# CC40_RAM_Cart.net
KiCad netlist of a schematic drawn in EAGLE
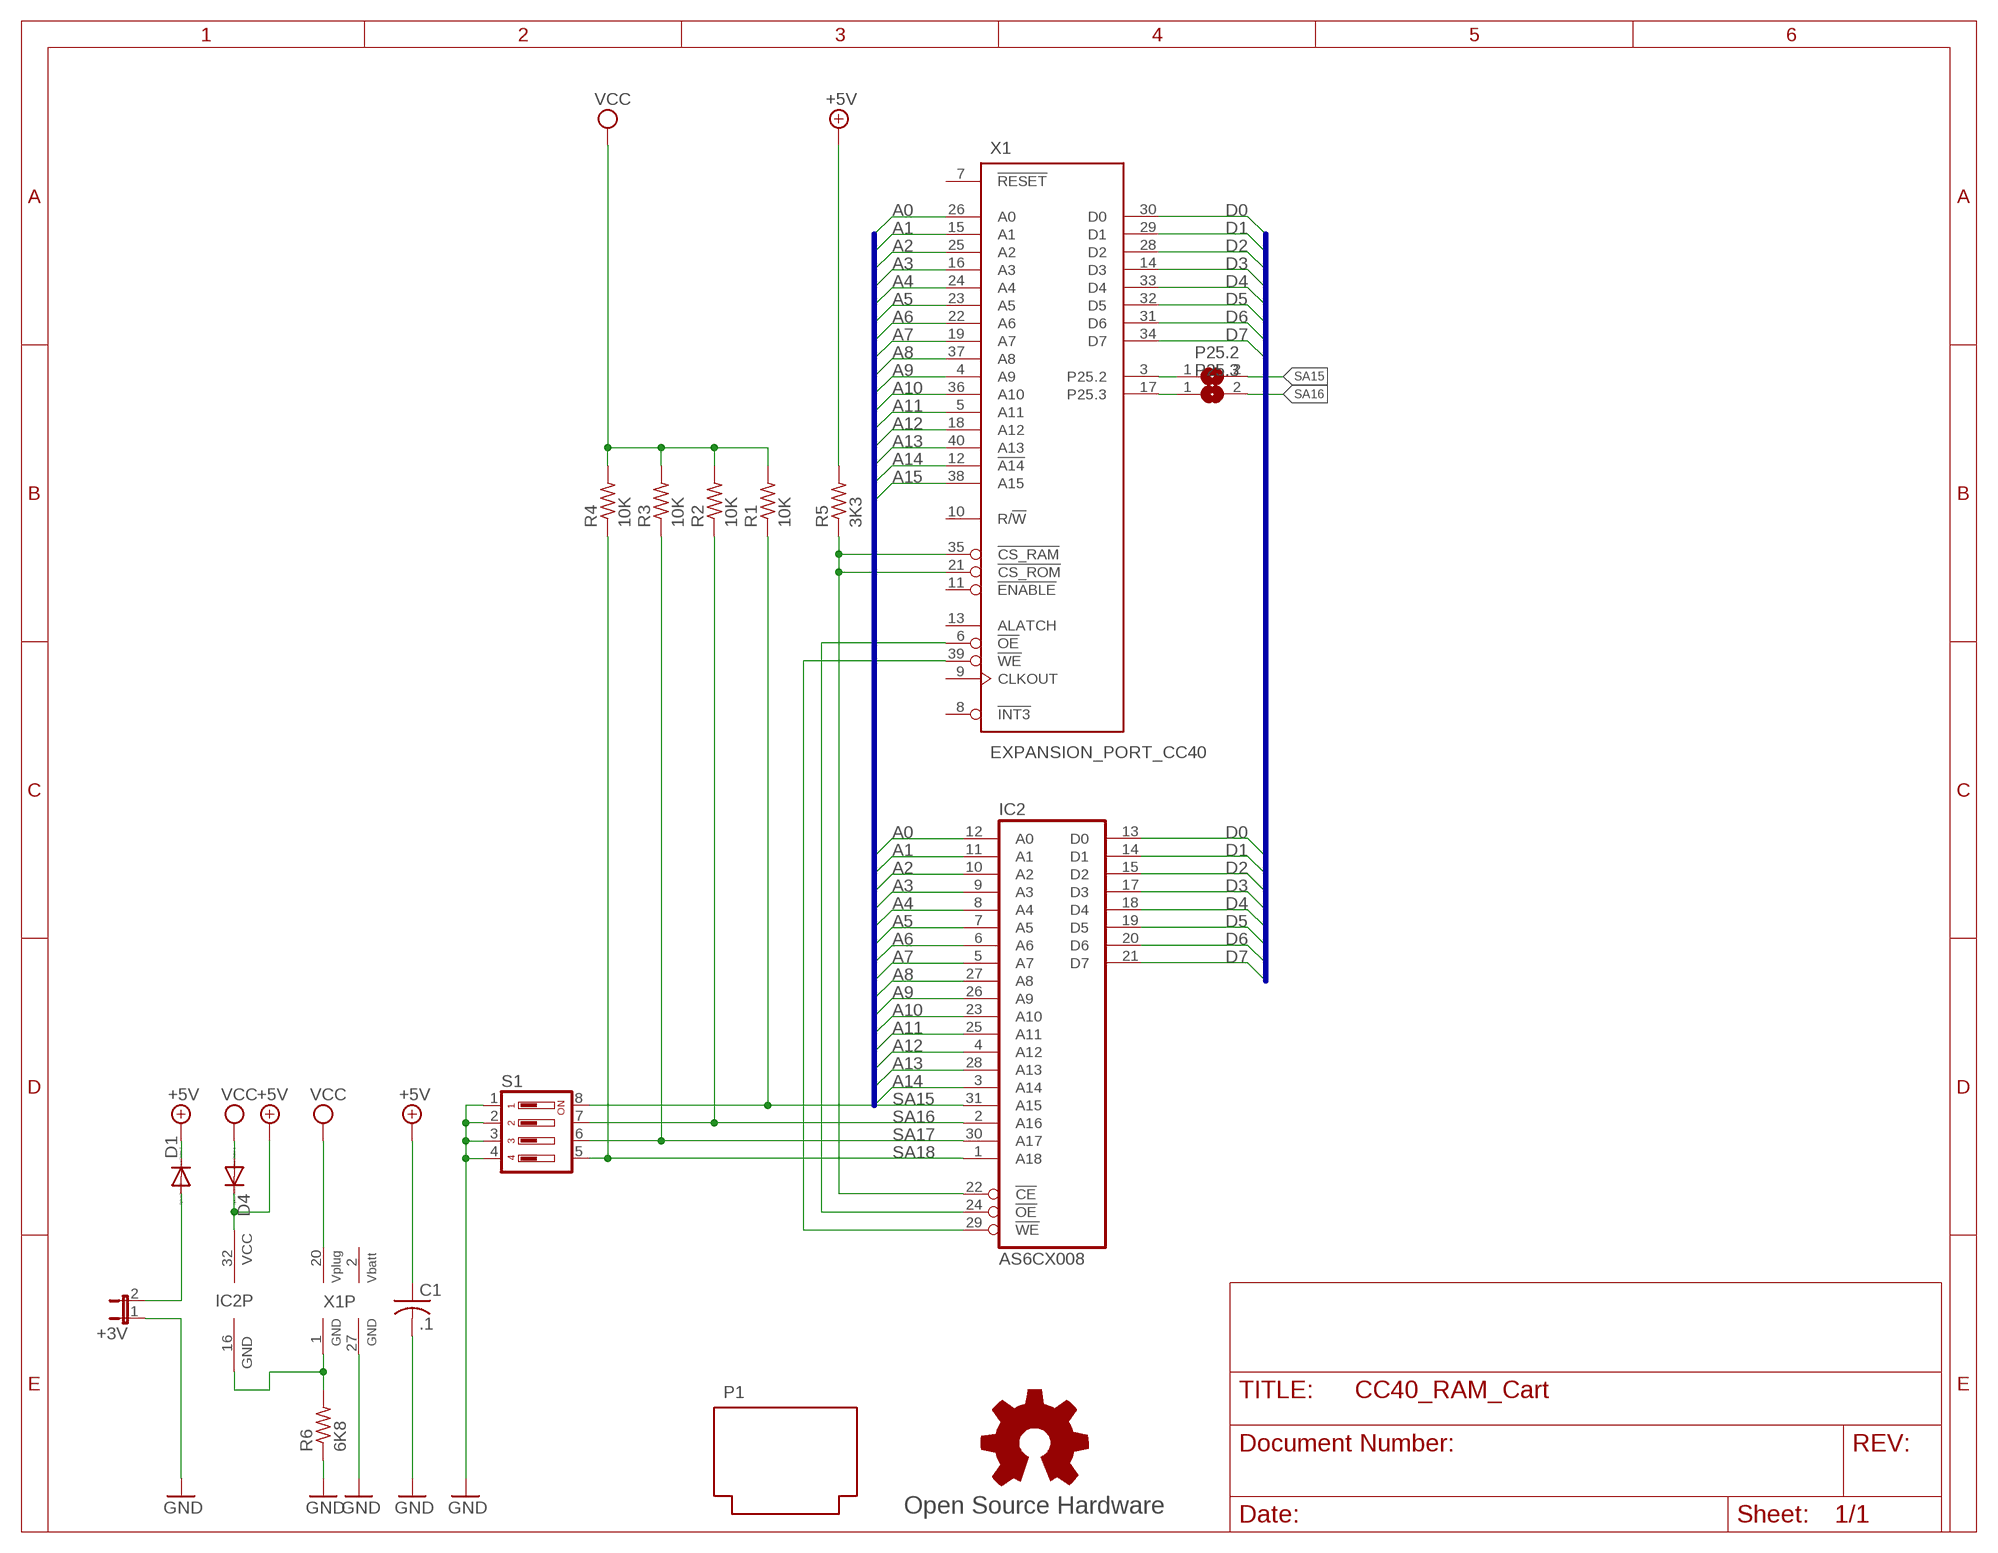
[diagram p0: schematic, sheet 1]

(export (version "E")
  (design (tool "Eeschema 10.0.6"))
  (components
    (comp (ref "+3V")
      (value "JP1E")
      (footprint "eagle-import:JP1")
      (libsource (lib "eagle-import") (part "JP1E"))
    )
    (comp (ref "C1")
      (value ".1")
      (footprint "eagle-import:C025-025X050")
      (libsource (lib "eagle-import") (part "C-US025-025X050"))
    )
    (comp (ref "D1")
      (value "DIODE-D-5")
      (footprint "eagle-import:D-5")
      (libsource (lib "eagle-import") (part "DIODE-D-5"))
    )
    (comp (ref "D4")
      (value "DIODE-D-5")
      (footprint "eagle-import:D-5")
      (libsource (lib "eagle-import") (part "DIODE-D-5"))
    )
    (comp (ref "GOLD_ORB_SM1")
      (value "Open Source Hardware")
      (footprint "eagle-import:OSHW_8MM")
      (libsource (lib "eagle-import") (part "OSHWLOGOLOGO8MM"))
    )
    (comp (ref "IC2")
      (value "AS6CX008")
      (footprint "eagle-import:DIL32-RP")
      (libsource (lib "eagle-import") (part "AS6C4008PCNR"))
    )
    (comp (ref "P1")
      (value "CC40_CARTN")
      (footprint "eagle-import:CC40_CART_NOHOLE")
      (libsource (lib "eagle-import") (part "CC40_CARTN"))
    )
    (comp (ref "P25.2")
      (value "SJ")
      (footprint "eagle-import:SJ")
      (libsource (lib "eagle-import") (part "SJ"))
    )
    (comp (ref "P25.3")
      (value "SJ")
      (footprint "eagle-import:SJ")
      (libsource (lib "eagle-import") (part "SJ"))
    )
    (comp (ref "R1")
      (value "10K")
      (footprint "eagle-import:0204_7")
      (libsource (lib "eagle-import") (part "R-US_0204/7"))
    )
    (comp (ref "R2")
      (value "10K")
      (footprint "eagle-import:0204_7")
      (libsource (lib "eagle-import") (part "R-US_0204/7"))
    )
    (comp (ref "R3")
      (value "10K")
      (footprint "eagle-import:0204_7")
      (libsource (lib "eagle-import") (part "R-US_0204/7"))
    )
    (comp (ref "R4")
      (value "10K")
      (footprint "eagle-import:0204_7")
      (libsource (lib "eagle-import") (part "R-US_0204/7"))
    )
    (comp (ref "R5")
      (value "3K3")
      (footprint "eagle-import:0204_7")
      (libsource (lib "eagle-import") (part "R-US_0204/7"))
    )
    (comp (ref "R6")
      (value "6K8")
      (footprint "eagle-import:0204_7")
      (libsource (lib "eagle-import") (part "R-US_0204/7"))
    )
    (comp (ref "S1")
      (value "DP04")
      (footprint "eagle-import:DP-04")
      (libsource (lib "eagle-import") (part "DP04"))
    )
    (comp (ref "X1")
      (value "EXPANSION_PORT_CC40")
      (footprint "eagle-import:MA20-2(.050)")
      (libsource (lib "eagle-import") (part "EXPANSION_PORT_CC40"))
    )
  )
  (nets
    (net (code "1") (name "+5V") (class "Default")
      (node (ref "C1") (pin "1") (pinfunction "1_1") (pintype "passive"))
      (node (ref "D1") (pin "C") (pinfunction "C_C") (pintype "passive"))
      (node (ref "D4") (pin "C") (pinfunction "C_C") (pintype "passive"))
      (node (ref "IC2") (pin "32") (pinfunction "VCC_32") (pintype "power_in"))
      (node (ref "R5") (pin "2") (pinfunction "2_2") (pintype "passive"))
    )
    (net (code "2") (name "/A0") (class "Default")
      (node (ref "IC2") (pin "12") (pinfunction "A0_12") (pintype "input"))
      (node (ref "X1") (pin "26") (pinfunction "A0_26") (pintype "output"))
    )
    (net (code "3") (name "/A1") (class "Default")
      (node (ref "IC2") (pin "11") (pinfunction "A1_11") (pintype "input"))
      (node (ref "X1") (pin "15") (pinfunction "A1_15") (pintype "output"))
    )
    (net (code "4") (name "/A2") (class "Default")
      (node (ref "IC2") (pin "10") (pinfunction "A2_10") (pintype "input"))
      (node (ref "X1") (pin "25") (pinfunction "A2_25") (pintype "output"))
    )
    (net (code "5") (name "/A3") (class "Default")
      (node (ref "IC2") (pin "9") (pinfunction "A3_9") (pintype "input"))
      (node (ref "X1") (pin "16") (pinfunction "A3_16") (pintype "output"))
    )
    (net (code "6") (name "/A4") (class "Default")
      (node (ref "IC2") (pin "8") (pinfunction "A4_8") (pintype "input"))
      (node (ref "X1") (pin "24") (pinfunction "A4_24") (pintype "output"))
    )
    (net (code "7") (name "/A5") (class "Default")
      (node (ref "IC2") (pin "7") (pinfunction "A5_7") (pintype "input"))
      (node (ref "X1") (pin "23") (pinfunction "A5_23") (pintype "output"))
    )
    (net (code "8") (name "/A6") (class "Default")
      (node (ref "IC2") (pin "6") (pinfunction "A6_6") (pintype "input"))
      (node (ref "X1") (pin "22") (pinfunction "A6_22") (pintype "output"))
    )
    (net (code "9") (name "/A7") (class "Default")
      (node (ref "IC2") (pin "5") (pinfunction "A7_5") (pintype "input"))
      (node (ref "X1") (pin "19") (pinfunction "A7_19") (pintype "output"))
    )
    (net (code "10") (name "/A8") (class "Default")
      (node (ref "IC2") (pin "27") (pinfunction "A8_27") (pintype "input"))
      (node (ref "X1") (pin "37") (pinfunction "A8_37") (pintype "output"))
    )
    (net (code "11") (name "/A9") (class "Default")
      (node (ref "IC2") (pin "26") (pinfunction "A9_26") (pintype "input"))
      (node (ref "X1") (pin "4") (pinfunction "A9_4") (pintype "output"))
    )
    (net (code "12") (name "/A10") (class "Default")
      (node (ref "IC2") (pin "23") (pinfunction "A10_23") (pintype "input"))
      (node (ref "X1") (pin "36") (pinfunction "A10_36") (pintype "passive"))
    )
    (net (code "13") (name "/A11") (class "Default")
      (node (ref "IC2") (pin "25") (pinfunction "A11_25") (pintype "input"))
      (node (ref "X1") (pin "5") (pinfunction "A11_5") (pintype "output"))
    )
    (net (code "14") (name "/A12") (class "Default")
      (node (ref "IC2") (pin "4") (pinfunction "A12_4") (pintype "input"))
      (node (ref "X1") (pin "18") (pinfunction "A12_18") (pintype "output"))
    )
    (net (code "15") (name "/A13") (class "Default")
      (node (ref "IC2") (pin "28") (pinfunction "A13_28") (pintype "input"))
      (node (ref "X1") (pin "40") (pinfunction "A13_40") (pintype "output"))
    )
    (net (code "16") (name "/A14") (class "Default")
      (node (ref "IC2") (pin "3") (pinfunction "A14_3") (pintype "input"))
      (node (ref "X1") (pin "12") (pinfunction "~{A14}_12") (pintype "output"))
    )
    (net (code "17") (name "/A15") (class "Default")
      (node (ref "X1") (pin "38") (pinfunction "A15_38") (pintype "output"))
    )
    (net (code "18") (name "/D0") (class "Default")
      (node (ref "IC2") (pin "13") (pinfunction "D0_13") (pintype "bidirectional"))
      (node (ref "X1") (pin "30") (pinfunction "D0_30") (pintype "bidirectional"))
    )
    (net (code "19") (name "/D1") (class "Default")
      (node (ref "IC2") (pin "14") (pinfunction "D1_14") (pintype "bidirectional"))
      (node (ref "X1") (pin "29") (pinfunction "D1_29") (pintype "bidirectional"))
    )
    (net (code "20") (name "/D2") (class "Default")
      (node (ref "IC2") (pin "15") (pinfunction "D2_15") (pintype "bidirectional"))
      (node (ref "X1") (pin "28") (pinfunction "D2_28") (pintype "bidirectional"))
    )
    (net (code "21") (name "/D3") (class "Default")
      (node (ref "IC2") (pin "17") (pinfunction "D3_17") (pintype "bidirectional"))
      (node (ref "X1") (pin "14") (pinfunction "D3_14") (pintype "bidirectional"))
    )
    (net (code "22") (name "/D4") (class "Default")
      (node (ref "IC2") (pin "18") (pinfunction "D4_18") (pintype "bidirectional"))
      (node (ref "X1") (pin "33") (pinfunction "D4_33") (pintype "bidirectional"))
    )
    (net (code "23") (name "/D5") (class "Default")
      (node (ref "IC2") (pin "19") (pinfunction "D5_19") (pintype "bidirectional"))
      (node (ref "X1") (pin "32") (pinfunction "D5_32") (pintype "bidirectional"))
    )
    (net (code "24") (name "/D6") (class "Default")
      (node (ref "IC2") (pin "20") (pinfunction "D6_20") (pintype "bidirectional"))
      (node (ref "X1") (pin "31") (pinfunction "D6_31") (pintype "bidirectional"))
    )
    (net (code "25") (name "/D7") (class "Default")
      (node (ref "IC2") (pin "21") (pinfunction "D7_21") (pintype "bidirectional"))
      (node (ref "X1") (pin "34") (pinfunction "D7_34") (pintype "bidirectional"))
    )
    (net (code "26") (name "/SA17") (class "Default")
      (node (ref "IC2") (pin "30") (pinfunction "A17_30") (pintype "input"))
      (node (ref "R3") (pin "1") (pinfunction "1_1") (pintype "passive"))
      (node (ref "S1") (pin "6") (pinfunction "6_6") (pintype "passive"))
    )
    (net (code "27") (name "/SA18") (class "Default")
      (node (ref "IC2") (pin "1") (pinfunction "A18_1") (pintype "input"))
      (node (ref "R4") (pin "1") (pinfunction "1_1") (pintype "passive"))
      (node (ref "S1") (pin "5") (pinfunction "5_5") (pintype "passive"))
    )
    (net (code "28") (name "/VBATT") (class "Default")
      (node (ref "X1") (pin "2") (pinfunction "VBATT_2") (pintype "power_in"))
    )
    (net (code "29") (name "GND") (class "Default")
      (node (ref "+3V") (pin "1") (pinfunction "1_1") (pintype "passive"))
      (node (ref "C1") (pin "2") (pinfunction "2_2") (pintype "passive"))
      (node (ref "R6") (pin "1") (pinfunction "1_1") (pintype "passive"))
      (node (ref "S1") (pin "1") (pinfunction "1_1") (pintype "passive"))
      (node (ref "S1") (pin "2") (pinfunction "2_2") (pintype "passive"))
      (node (ref "S1") (pin "3") (pinfunction "3_3") (pintype "passive"))
      (node (ref "S1") (pin "4") (pinfunction "4_4") (pintype "passive"))
      (node (ref "X1") (pin "27") (pinfunction "GND_27") (pintype "power_in"))
    )
    (net (code "30") (name "Net-(+3V-Pad2)") (class "Default")
      (node (ref "+3V") (pin "2") (pinfunction "2_2") (pintype "passive"))
      (node (ref "D1") (pin "A") (pinfunction "A_A") (pintype "passive"))
    )
    (net (code "31") (name "Net-(IC2A-~{CE})") (class "Default")
      (node (ref "IC2") (pin "22") (pinfunction "~{CE}_22") (pintype "input"))
      (node (ref "R5") (pin "1") (pinfunction "1_1") (pintype "passive"))
      (node (ref "X1") (pin "21") (pinfunction "~{CS_ROM}_21") (pintype "output"))
      (node (ref "X1") (pin "35") (pinfunction "~{CS_RAM}_35") (pintype "output"))
    )
    (net (code "32") (name "Net-(IC2A-~{OE})") (class "Default")
      (node (ref "IC2") (pin "24") (pinfunction "~{OE}_24") (pintype "input"))
      (node (ref "X1") (pin "6") (pinfunction "~{OE}_6") (pintype "output"))
    )
    (net (code "33") (name "Net-(IC2A-~{WE})") (class "Default")
      (node (ref "IC2") (pin "29") (pinfunction "~{WE}_29") (pintype "input"))
      (node (ref "X1") (pin "39") (pinfunction "~{WE}_39") (pintype "output"))
    )
    (net (code "34") (name "Net-(IC2B-GND)") (class "Default")
      (node (ref "IC2") (pin "16") (pinfunction "GND_16") (pintype "power_in"))
      (node (ref "R6") (pin "2") (pinfunction "2_2") (pintype "passive"))
      (node (ref "X1") (pin "1") (pinfunction "GND_1") (pintype "power_in"))
    )
    (net (code "35") (name "Net-(X1B-P25.2)") (class "Default")
      (node (ref "P25.2") (pin "1") (pinfunction "1_1") (pintype "passive"))
      (node (ref "X1") (pin "3") (pinfunction "P25.2_3") (pintype "bidirectional"))
    )
    (net (code "36") (name "Net-(X1B-P25.3)") (class "Default")
      (node (ref "P25.3") (pin "1") (pinfunction "1_1") (pintype "passive"))
      (node (ref "X1") (pin "17") (pinfunction "P25.3_17") (pintype "bidirectional"))
    )
    (net (code "37") (name "SA15") (class "Default")
      (node (ref "IC2") (pin "31") (pinfunction "A15_31") (pintype "input"))
      (node (ref "P25.2") (pin "2") (pinfunction "2_2") (pintype "passive"))
      (node (ref "R1") (pin "1") (pinfunction "1_1") (pintype "passive"))
      (node (ref "S1") (pin "8") (pinfunction "8_8") (pintype "passive"))
    )
    (net (code "38") (name "SA16") (class "Default")
      (node (ref "IC2") (pin "2") (pinfunction "A16_2") (pintype "input"))
      (node (ref "P25.3") (pin "2") (pinfunction "2_2") (pintype "passive"))
      (node (ref "R2") (pin "1") (pinfunction "1_1") (pintype "passive"))
      (node (ref "S1") (pin "7") (pinfunction "7_7") (pintype "passive"))
    )
    (net (code "39") (name "VCC") (class "Default")
      (node (ref "D4") (pin "A") (pinfunction "A_A") (pintype "passive"))
      (node (ref "R1") (pin "2") (pinfunction "2_2") (pintype "passive"))
      (node (ref "R2") (pin "2") (pinfunction "2_2") (pintype "passive"))
      (node (ref "R3") (pin "2") (pinfunction "2_2") (pintype "passive"))
      (node (ref "R4") (pin "2") (pinfunction "2_2") (pintype "passive"))
      (node (ref "X1") (pin "20") (pinfunction "VPLUG_20") (pintype "power_in"))
    )
    (net (code "40") (name "unconnected-(X1B-ALATCH-Pad13)") (class "Default")
      (node (ref "X1") (pin "13") (pinfunction "ALATCH_13") (pintype "output"))
    )
    (net (code "41") (name "unconnected-(X1B-CLKOUT-Pad9)") (class "Default")
      (node (ref "X1") (pin "9") (pinfunction "CLKOUT_9") (pintype "output"))
    )
    (net (code "42") (name "unconnected-(X1B-R{slash}~{W}-Pad10)") (class "Default")
      (node (ref "X1") (pin "10") (pinfunction "R/~{W}_10") (pintype "output"))
    )
    (net (code "43") (name "unconnected-(X1B-~{ENABLE}-Pad11)") (class "Default")
      (node (ref "X1") (pin "11") (pinfunction "~{ENABLE}_11") (pintype "output"))
    )
    (net (code "44") (name "unconnected-(X1B-~{INT3}-Pad8)") (class "Default")
      (node (ref "X1") (pin "8") (pinfunction "~{INT3}_8") (pintype "open_collector"))
    )
    (net (code "45") (name "unconnected-(X1B-~{RESET}-Pad7)") (class "Default")
      (node (ref "X1") (pin "7") (pinfunction "~{RESET}_7") (pintype "open_collector"))
    )
  )
)
